# ET4207_DEMO.net
KiCad netlist of a schematic drawn in Altium Designer
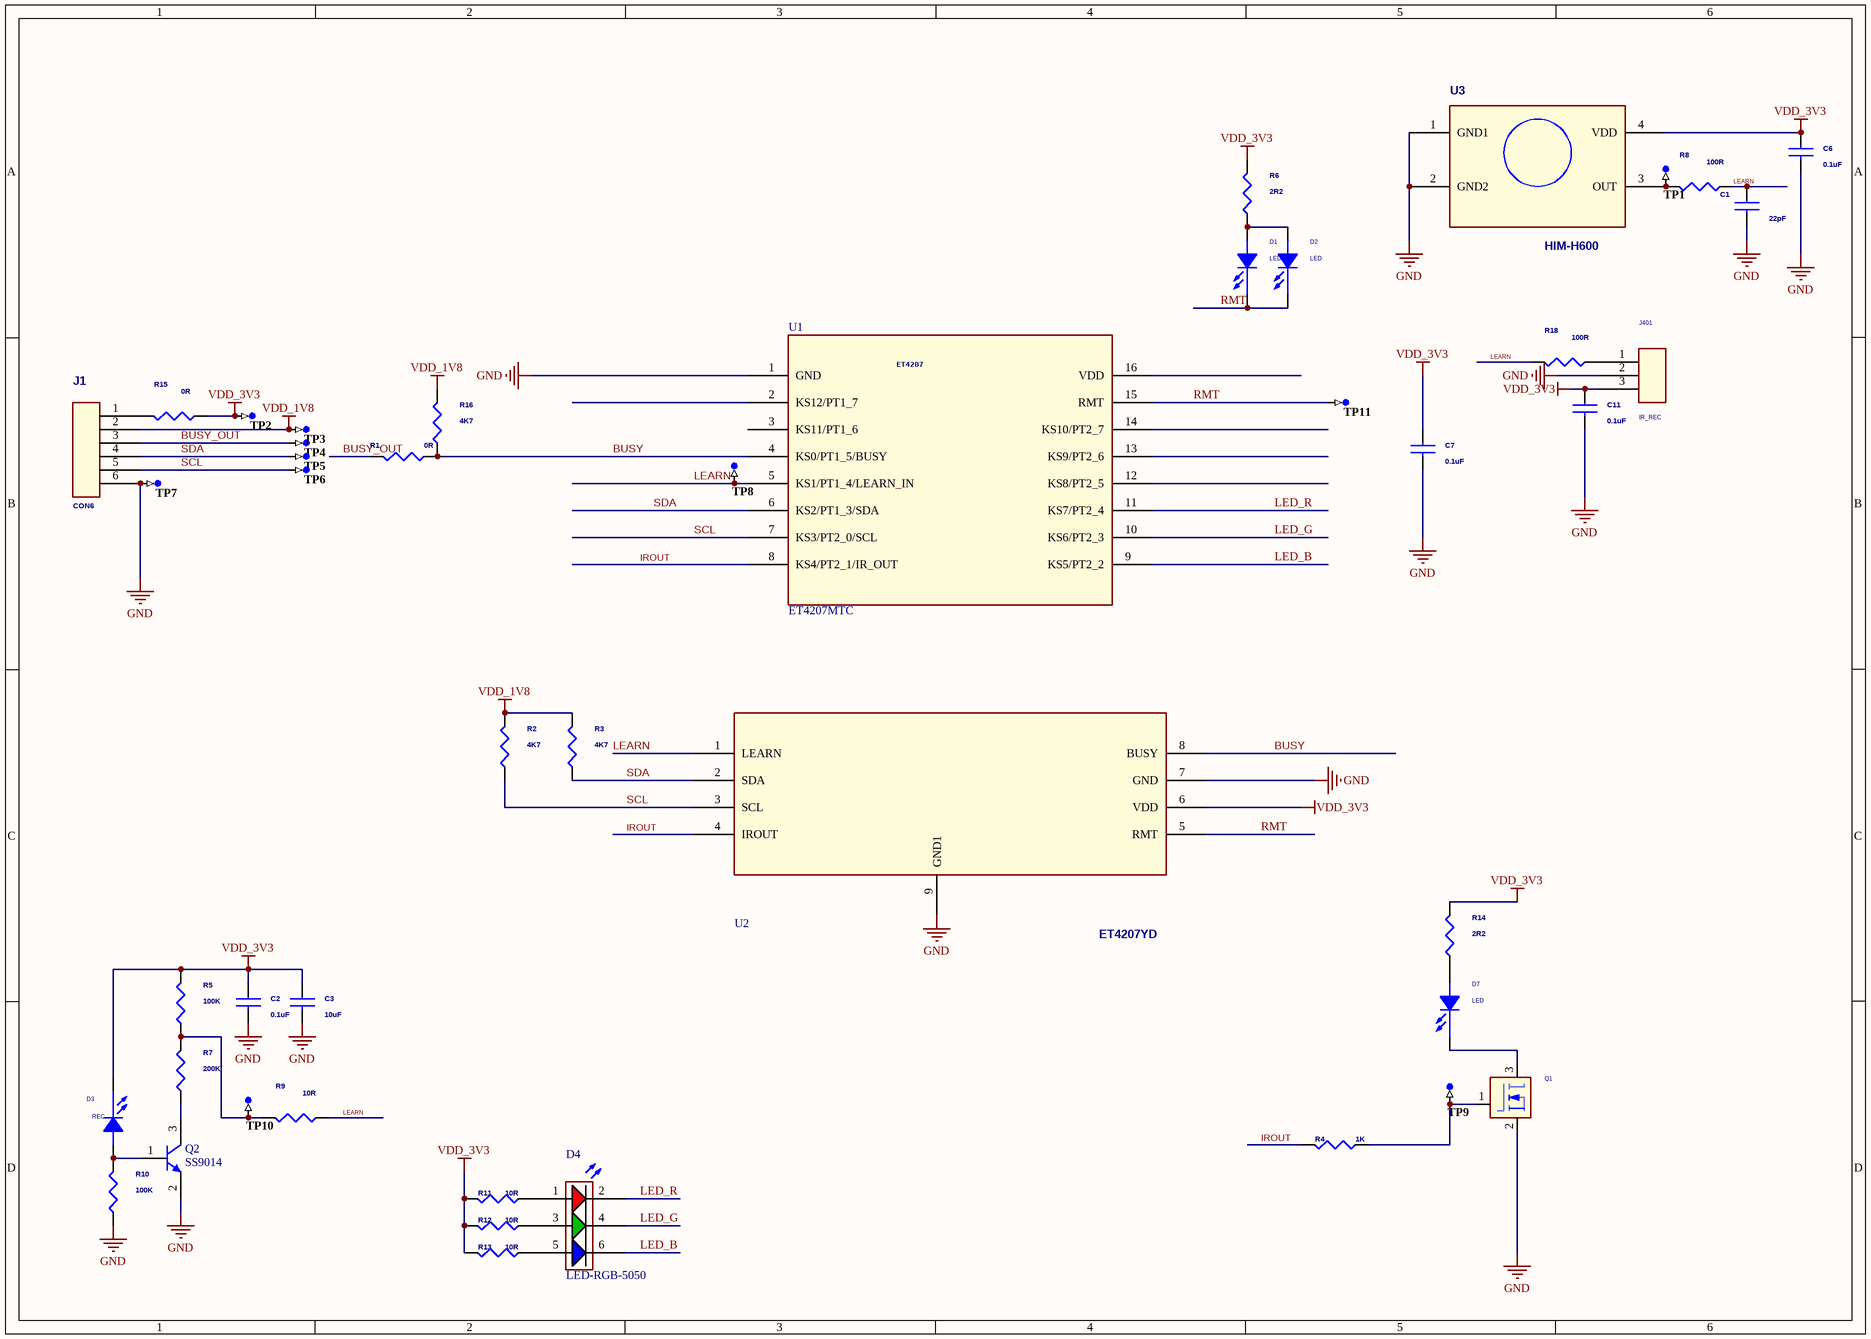
[diagram p0: ET4207_DEMO.SchDoc]

(export (version "E")
  (design (tool "Eeschema 10.0.6"))
  (components
    (comp (ref "C1") (value "22pF") (footprint "0805C") (libsource (lib "*") (part "CAPACITOR NON-POL")))
    (comp (ref "C2") (value "0.1uF") (footprint "0805C") (libsource (lib "*") (part "CAPACITOR NON-POL")))
    (comp (ref "C3") (value "10uF") (footprint "0805C") (libsource (lib "*") (part "CAPACITOR NON-POL")))
    (comp (ref "C6") (value "0.1uF") (footprint "0805C") (libsource (lib "*") (part "CAPACITOR NON-POL")))
    (comp (ref "C7") (value "0.1uF") (footprint "0805C") (libsource (lib "*") (part "CAPACITOR NON-POL")))
    (comp (ref "C11") (value "0.1uF") (footprint "0805C") (libsource (lib "*") (part "CAPACITOR NON-POL")))
    (comp (ref "D1") (value "LED") (footprint "LED_A2") (libsource (lib "*") (part "LED_3")))
    (comp (ref "D2") (value "LED") (footprint "LED-0805") (libsource (lib "*") (part "LED_3")))
    (comp (ref "D3") (value "REC") (footprint "LED_A2") (libsource (lib "*") (part "LED_3")))
    (comp (ref "D4")
      (value "LED-RGB-5050")
      (footprint "LED-5050")
      (description "三基色LED")
      (fields (field (name "PUBLISHER") "Altium Limited"))
      (libsource (lib "sommer") (part "LED-RGB-5050"))
    )
    (comp (ref "D7") (value "LED") (footprint "LED_A2") (libsource (lib "*") (part "LED_3")))
    (comp (ref "J1") (value "CON6") (footprint "HDR1X6") (libsource (lib "*") (part "CON6")))
    (comp (ref "J401") (value "IR_REC") (footprint "IR") (libsource (lib "*") (part "CON3_0")))
    (comp (ref "Q1")
      (value "BSS138LT3G")
      (footprint "SOT-23")
      (description "MOSFET N-CH 50V 200MA SOT-23")
      (fields
        (field (name "TI_PART_NO") "TI-MOS-BSS138LT3G")
        (field (name "DISTRIBUTOR_PART_NUMBER") "BSS138LT3GOSCT-ND")
      )
      (libsource (lib "*") (part "MOSFET_I_EN_GSD"))
    )
    (comp (ref "Q2")
      (value "SS9014")
      (footprint "SOT23-3")
      (description "NPN贴片三极管")
      (fields (field (name "PUBLISHER") "Altium Limited"))
      (libsource (lib "sommer") (part "SS9014"))
    )
    (comp (ref "R1") (value "0R") (footprint "0805R") (libsource (lib "*") (part "RESISTOR")))
    (comp (ref "R2") (value "4K7") (footprint "0805R") (libsource (lib "*") (part "RESISTOR")))
    (comp (ref "R3") (value "4K7") (footprint "0805R") (libsource (lib "*") (part "RESISTOR")))
    (comp (ref "R4") (value "1K") (footprint "0805R") (libsource (lib "*") (part "RESISTOR")))
    (comp (ref "R5") (value "100K") (footprint "0805R") (libsource (lib "*") (part "RESISTOR")))
    (comp (ref "R6") (value "2R2") (footprint "0805R") (libsource (lib "*") (part "RESISTOR")))
    (comp (ref "R7") (value "200K") (footprint "0805R") (libsource (lib "*") (part "RESISTOR")))
    (comp (ref "R8") (value "100R") (footprint "0805R") (libsource (lib "*") (part "RESISTOR")))
    (comp (ref "R9") (value "10R") (footprint "0805R") (libsource (lib "*") (part "RESISTOR")))
    (comp (ref "R10") (value "100K") (footprint "0805R") (libsource (lib "*") (part "RESISTOR")))
    (comp (ref "R11") (value "10R") (footprint "0805R") (libsource (lib "*") (part "RESISTOR")))
    (comp (ref "R12") (value "10R") (footprint "0805R") (libsource (lib "*") (part "RESISTOR")))
    (comp (ref "R13") (value "10R") (footprint "0805R") (libsource (lib "*") (part "RESISTOR")))
    (comp (ref "R14") (value "2R2") (footprint "0805R") (libsource (lib "*") (part "RESISTOR")))
    (comp (ref "R15") (value "0R") (footprint "0805R") (libsource (lib "*") (part "RESISTOR")))
    (comp (ref "R16") (value "4K7") (footprint "0805R") (libsource (lib "*") (part "RESISTOR")))
    (comp (ref "R18") (value "100R") (footprint "0805R") (libsource (lib "*") (part "RESISTOR")))
    (comp (ref "TP1")
      (value "PULSE")
      (footprint "TP-SM-C-100")
      (description "Test Point, Surface Mount, Circular, Pad Diameter 1 mm")
      (libsource (lib "sommer") (part "TP-SM"))
    )
    (comp (ref "TP2")
      (value "3V3")
      (footprint "TP-SM-C-100")
      (description "Test Point, Surface Mount, Circular, Pad Diameter 1 mm")
      (libsource (lib "sommer") (part "TP-SM"))
    )
    (comp (ref "TP3")
      (value "1V8")
      (footprint "TP-SM-C-100")
      (description "Test Point, Surface Mount, Circular, Pad Diameter 1 mm")
      (libsource (lib "sommer") (part "TP-SM"))
    )
    (comp (ref "TP4")
      (value "BUSY")
      (footprint "TP-SM-C-100")
      (description "Test Point, Surface Mount, Circular, Pad Diameter 1 mm")
      (libsource (lib "sommer") (part "TP-SM"))
    )
    (comp (ref "TP5")
      (value "SDA")
      (footprint "TP-SM-C-100")
      (description "Test Point, Surface Mount, Circular, Pad Diameter 1 mm")
      (libsource (lib "sommer") (part "TP-SM"))
    )
    (comp (ref "TP6")
      (value "SCL")
      (footprint "TP-SM-C-100")
      (description "Test Point, Surface Mount, Circular, Pad Diameter 1 mm")
      (libsource (lib "sommer") (part "TP-SM"))
    )
    (comp (ref "TP7")
      (value "GND")
      (footprint "TP-SM-C-100")
      (description "Test Point, Surface Mount, Circular, Pad Diameter 1 mm")
      (libsource (lib "sommer") (part "TP-SM"))
    )
    (comp (ref "TP8")
      (value "LEARN")
      (footprint "TP-SM-C-100")
      (description "Test Point, Surface Mount, Circular, Pad Diameter 1 mm")
      (libsource (lib "sommer") (part "TP-SM"))
    )
    (comp (ref "TP9")
      (value "IROUT")
      (footprint "TP-SM-C-100")
      (description "Test Point, Surface Mount, Circular, Pad Diameter 1 mm")
      (libsource (lib "sommer") (part "TP-SM"))
    )
    (comp (ref "TP10")
      (value "DIODE_V")
      (footprint "TP-SM-C-100")
      (description "Test Point, Surface Mount, Circular, Pad Diameter 1 mm")
      (libsource (lib "sommer") (part "TP-SM"))
    )
    (comp (ref "TP11")
      (value "RMT")
      (footprint "TP-SM-C-100")
      (description "Test Point, Surface Mount, Circular, Pad Diameter 1 mm")
      (libsource (lib "sommer") (part "TP-SM"))
    )
    (comp (ref "U1")
      (value "ET4207MTC")
      (footprint "sommer:soic-16")
      (libsource (lib "ET4207_DEMO_Library") (part "ET4207MTC"))
    )
    (comp (ref "U2")
      (value "ET4207YD")
      (footprint "QFN-8")
      (libsource (lib "ET4207_DEMO_Library") (part "ET4207YD"))
    )
    (comp (ref "U3") (value "HIM-H600") (footprint "HIM-H600") (libsource (lib "*") (part "LPC111x_7")))
  )
  (nets
    (net (code "1") (name "/BUSY") (class "Default")
      (node (ref "R1") (pin "1") (pinfunction "1_1") (pintype "passive"))
      (node (ref "R16") (pin "1") (pinfunction "1_1") (pintype "passive"))
      (node (ref "U1") (pin "4") (pinfunction "KS0/PT1_5/BUSY_4") (pintype "passive"))
      (node (ref "U2") (pin "8") (pinfunction "BUSY_8") (pintype "passive"))
    )
    (net (code "2") (name "/BUSY_OUT") (class "Default")
      (node (ref "J1") (pin "3") (pinfunction "3_3") (pintype "passive"))
      (node (ref "R1") (pin "2") (pinfunction "2_2") (pintype "passive"))
      (node (ref "TP4") (pin "1") (pinfunction "1_1") (pintype "input"))
    )
    (net (code "3") (name "/IROUT") (class "Default")
      (node (ref "R4") (pin "2") (pinfunction "2_2") (pintype "passive"))
      (node (ref "U1") (pin "8") (pinfunction "KS4/PT2_1/IR_OUT_8") (pintype "passive"))
      (node (ref "U2") (pin "4") (pinfunction "IROUT_4") (pintype "passive"))
    )
    (net (code "4") (name "/LEARN") (class "Default")
      (node (ref "C1") (pin "1") (pinfunction "1_1") (pintype "passive"))
      (node (ref "R18") (pin "2") (pinfunction "2_2") (pintype "passive"))
      (node (ref "R8") (pin "1") (pinfunction "1_1") (pintype "passive"))
      (node (ref "R9") (pin "1") (pinfunction "1_1") (pintype "passive"))
      (node (ref "TP8") (pin "1") (pinfunction "1_1") (pintype "input"))
      (node (ref "U1") (pin "5") (pinfunction "KS1/PT1_4/LEARN_IN_5") (pintype "passive"))
      (node (ref "U2") (pin "1") (pinfunction "LEARN_1") (pintype "passive"))
    )
    (net (code "5") (name "/LED_B") (class "Default")
      (node (ref "D4") (pin "6") (pinfunction "B_6") (pintype "passive"))
      (node (ref "U1") (pin "9") (pinfunction "KS5/PT2_2_9") (pintype "passive"))
    )
    (net (code "6") (name "/LED_G") (class "Default")
      (node (ref "D4") (pin "4") (pinfunction "G_4") (pintype "passive"))
      (node (ref "U1") (pin "10") (pinfunction "KS6/PT2_3_10") (pintype "passive"))
    )
    (net (code "7") (name "/LED_R") (class "Default")
      (node (ref "D4") (pin "2") (pinfunction "R_2") (pintype "passive"))
      (node (ref "U1") (pin "11") (pinfunction "KS7/PT2_4_11") (pintype "passive"))
    )
    (net (code "8") (name "/RMT") (class "Default")
      (node (ref "D1") (pin "2") (pinfunction "CATHODE_2") (pintype "passive"))
      (node (ref "D2") (pin "2") (pinfunction "CATHODE_2") (pintype "passive"))
      (node (ref "TP11") (pin "1") (pinfunction "1_1") (pintype "input"))
      (node (ref "U1") (pin "15") (pinfunction "RMT_15") (pintype "passive"))
      (node (ref "U2") (pin "5") (pinfunction "RMT_5") (pintype "passive"))
    )
    (net (code "9") (name "/SCL") (class "Default")
      (node (ref "J1") (pin "5") (pinfunction "5_5") (pintype "passive"))
      (node (ref "R2") (pin "1") (pinfunction "1_1") (pintype "passive"))
      (node (ref "TP6") (pin "1") (pinfunction "1_1") (pintype "input"))
      (node (ref "U1") (pin "7") (pinfunction "KS3/PT2_0/SCL_7") (pintype "passive"))
      (node (ref "U2") (pin "3") (pinfunction "SCL_3") (pintype "passive"))
    )
    (net (code "10") (name "/SDA") (class "Default")
      (node (ref "J1") (pin "4") (pinfunction "4_4") (pintype "passive"))
      (node (ref "R3") (pin "1") (pinfunction "1_1") (pintype "passive"))
      (node (ref "TP5") (pin "1") (pinfunction "1_1") (pintype "input"))
      (node (ref "U1") (pin "6") (pinfunction "KS2/PT1_3/SDA_6") (pintype "passive"))
      (node (ref "U2") (pin "2") (pinfunction "SDA_2") (pintype "passive"))
    )
    (net (code "11") (name "GND") (class "Default")
      (node (ref "C1") (pin "2") (pinfunction "2_2") (pintype "passive"))
      (node (ref "C11") (pin "2") (pinfunction "2_2") (pintype "passive"))
      (node (ref "C2") (pin "2") (pinfunction "2_2") (pintype "passive"))
      (node (ref "C3") (pin "2") (pinfunction "2_2") (pintype "passive"))
      (node (ref "C6") (pin "2") (pinfunction "2_2") (pintype "passive"))
      (node (ref "C7") (pin "2") (pinfunction "2_2") (pintype "passive"))
      (node (ref "J1") (pin "6") (pinfunction "6_6") (pintype "passive"))
      (node (ref "J401") (pin "2") (pinfunction "GND_2") (pintype "passive"))
      (node (ref "Q1") (pin "2") (pinfunction "S_2") (pintype "passive"))
      (node (ref "Q2") (pin "2") (pinfunction "E_2") (pintype "passive"))
      (node (ref "R10") (pin "1") (pinfunction "1_1") (pintype "passive"))
      (node (ref "TP7") (pin "1") (pinfunction "1_1") (pintype "input"))
      (node (ref "U1") (pin "1") (pinfunction "GND_1") (pintype "passive"))
      (node (ref "U2") (pin "7") (pinfunction "GND_7") (pintype "passive"))
      (node (ref "U2") (pin "9") (pinfunction "GND1_9") (pintype "passive"))
      (node (ref "U3") (pin "1") (pinfunction "GND1_1") (pintype "passive"))
      (node (ref "U3") (pin "2") (pinfunction "GND2_2") (pintype "passive"))
    )
    (net (code "12") (name "Net-(D1-ANODE)") (class "Default")
      (node (ref "D1") (pin "1") (pinfunction "ANODE_1") (pintype "passive"))
      (node (ref "D2") (pin "1") (pinfunction "ANODE_1") (pintype "passive"))
      (node (ref "R6") (pin "1") (pinfunction "1_1") (pintype "passive"))
    )
    (net (code "13") (name "Net-(D3-ANODE)") (class "Default")
      (node (ref "D3") (pin "1") (pinfunction "ANODE_1") (pintype "passive"))
      (node (ref "Q2") (pin "1") (pinfunction "B_1") (pintype "passive"))
      (node (ref "R10") (pin "2") (pinfunction "2_2") (pintype "passive"))
    )
    (net (code "14") (name "Net-(D4-A)") (class "Default")
      (node (ref "D4") (pin "3") (pinfunction "A_3") (pintype "passive"))
      (node (ref "R12") (pin "1") (pinfunction "1_1") (pintype "passive"))
    )
    (net (code "15") (name "Net-(D4-R-Pad1)") (class "Default")
      (node (ref "D4") (pin "1") (pinfunction "R_1") (pintype "passive"))
      (node (ref "R11") (pin "1") (pinfunction "1_1") (pintype "passive"))
    )
    (net (code "16") (name "Net-(D4-R-Pad5)") (class "Default")
      (node (ref "D4") (pin "5") (pinfunction "R_5") (pintype "passive"))
      (node (ref "R13") (pin "1") (pinfunction "1_1") (pintype "passive"))
    )
    (net (code "17") (name "Net-(D7-ANODE)") (class "Default")
      (node (ref "D7") (pin "1") (pinfunction "ANODE_1") (pintype "passive"))
      (node (ref "R14") (pin "1") (pinfunction "1_1") (pintype "passive"))
    )
    (net (code "18") (name "Net-(D7-CATHODE)") (class "Default")
      (node (ref "D7") (pin "2") (pinfunction "CATHODE_2") (pintype "passive"))
      (node (ref "Q1") (pin "3") (pinfunction "D_3") (pintype "passive"))
    )
    (net (code "19") (name "Net-(J1-Pad1)") (class "Default")
      (node (ref "J1") (pin "1") (pinfunction "1_1") (pintype "passive"))
      (node (ref "R15") (pin "2") (pinfunction "2_2") (pintype "passive"))
    )
    (net (code "20") (name "Net-(J401-IROUT)") (class "Default")
      (node (ref "J401") (pin "1") (pinfunction "IROUT_1") (pintype "passive"))
      (node (ref "R18") (pin "1") (pinfunction "1_1") (pintype "passive"))
    )
    (net (code "21") (name "Net-(Q1-G)") (class "Default")
      (node (ref "Q1") (pin "1") (pinfunction "G_1") (pintype "passive"))
      (node (ref "R4") (pin "1") (pinfunction "1_1") (pintype "passive"))
      (node (ref "TP9") (pin "1") (pinfunction "1_1") (pintype "input"))
    )
    (net (code "22") (name "Net-(Q2-C)") (class "Default")
      (node (ref "Q2") (pin "3") (pinfunction "C_3") (pintype "passive"))
      (node (ref "R7") (pin "1") (pinfunction "1_1") (pintype "passive"))
    )
    (net (code "23") (name "Net-(R5-Pad1)") (class "Default")
      (node (ref "R5") (pin "1") (pinfunction "1_1") (pintype "passive"))
      (node (ref "R7") (pin "2") (pinfunction "2_2") (pintype "passive"))
      (node (ref "R9") (pin "2") (pinfunction "2_2") (pintype "passive"))
      (node (ref "TP10") (pin "1") (pinfunction "1_1") (pintype "input"))
    )
    (net (code "24") (name "Net-(U3-OUT)") (class "Default")
      (node (ref "R8") (pin "2") (pinfunction "2_2") (pintype "passive"))
      (node (ref "TP1") (pin "1") (pinfunction "1_1") (pintype "input"))
      (node (ref "U3") (pin "3") (pinfunction "OUT_3") (pintype "passive"))
    )
    (net (code "25") (name "VDD_1V8") (class "Default")
      (node (ref "J1") (pin "2") (pinfunction "2_2") (pintype "passive"))
      (node (ref "R16") (pin "2") (pinfunction "2_2") (pintype "passive"))
      (node (ref "R2") (pin "2") (pinfunction "2_2") (pintype "passive"))
      (node (ref "R3") (pin "2") (pinfunction "2_2") (pintype "passive"))
      (node (ref "TP3") (pin "1") (pinfunction "1_1") (pintype "input"))
    )
    (net (code "26") (name "VDD_3V3") (class "Default")
      (node (ref "C11") (pin "1") (pinfunction "1_1") (pintype "passive"))
      (node (ref "C2") (pin "1") (pinfunction "1_1") (pintype "passive"))
      (node (ref "C3") (pin "1") (pinfunction "1_1") (pintype "passive"))
      (node (ref "C6") (pin "1") (pinfunction "1_1") (pintype "passive"))
      (node (ref "C7") (pin "1") (pinfunction "1_1") (pintype "passive"))
      (node (ref "D3") (pin "2") (pinfunction "CATHODE_2") (pintype "passive"))
      (node (ref "J401") (pin "3") (pinfunction "VCC_3") (pintype "passive"))
      (node (ref "R11") (pin "2") (pinfunction "2_2") (pintype "passive"))
      (node (ref "R12") (pin "2") (pinfunction "2_2") (pintype "passive"))
      (node (ref "R13") (pin "2") (pinfunction "2_2") (pintype "passive"))
      (node (ref "R14") (pin "2") (pinfunction "2_2") (pintype "passive"))
      (node (ref "R15") (pin "1") (pinfunction "1_1") (pintype "passive"))
      (node (ref "R5") (pin "2") (pinfunction "2_2") (pintype "passive"))
      (node (ref "R6") (pin "2") (pinfunction "2_2") (pintype "passive"))
      (node (ref "TP2") (pin "1") (pinfunction "1_1") (pintype "input"))
      (node (ref "U2") (pin "6") (pinfunction "VDD_6") (pintype "passive"))
      (node (ref "U3") (pin "4") (pinfunction "VDD_4") (pintype "passive"))
    )
    (net (code "27") (name "unconnected-(U1-KS8{slash}PT2_5-Pad12)") (class "Default")
      (node (ref "U1") (pin "12") (pinfunction "KS8/PT2_5_12") (pintype "passive"))
    )
    (net (code "28") (name "unconnected-(U1-KS9{slash}PT2_6-Pad13)") (class "Default")
      (node (ref "U1") (pin "13") (pinfunction "KS9/PT2_6_13") (pintype "passive"))
    )
    (net (code "29") (name "unconnected-(U1-KS10{slash}PT2_7-Pad14)") (class "Default")
      (node (ref "U1") (pin "14") (pinfunction "KS10/PT2_7_14") (pintype "passive"))
    )
    (net (code "30") (name "unconnected-(U1-KS11{slash}PT1_6-Pad3)") (class "Default")
      (node (ref "U1") (pin "3") (pinfunction "KS11/PT1_6_3") (pintype "passive"))
    )
    (net (code "31") (name "unconnected-(U1-KS12{slash}PT1_7-Pad2)") (class "Default")
      (node (ref "U1") (pin "2") (pinfunction "KS12/PT1_7_2") (pintype "passive"))
    )
    (net (code "32") (name "unconnected-(U1-VDD-Pad16)") (class "Default")
      (node (ref "U1") (pin "16") (pinfunction "VDD_16") (pintype "passive"))
    )
  )
)
